# schemes.net
KiCad netlist of a schematic drawn in EasyEDA
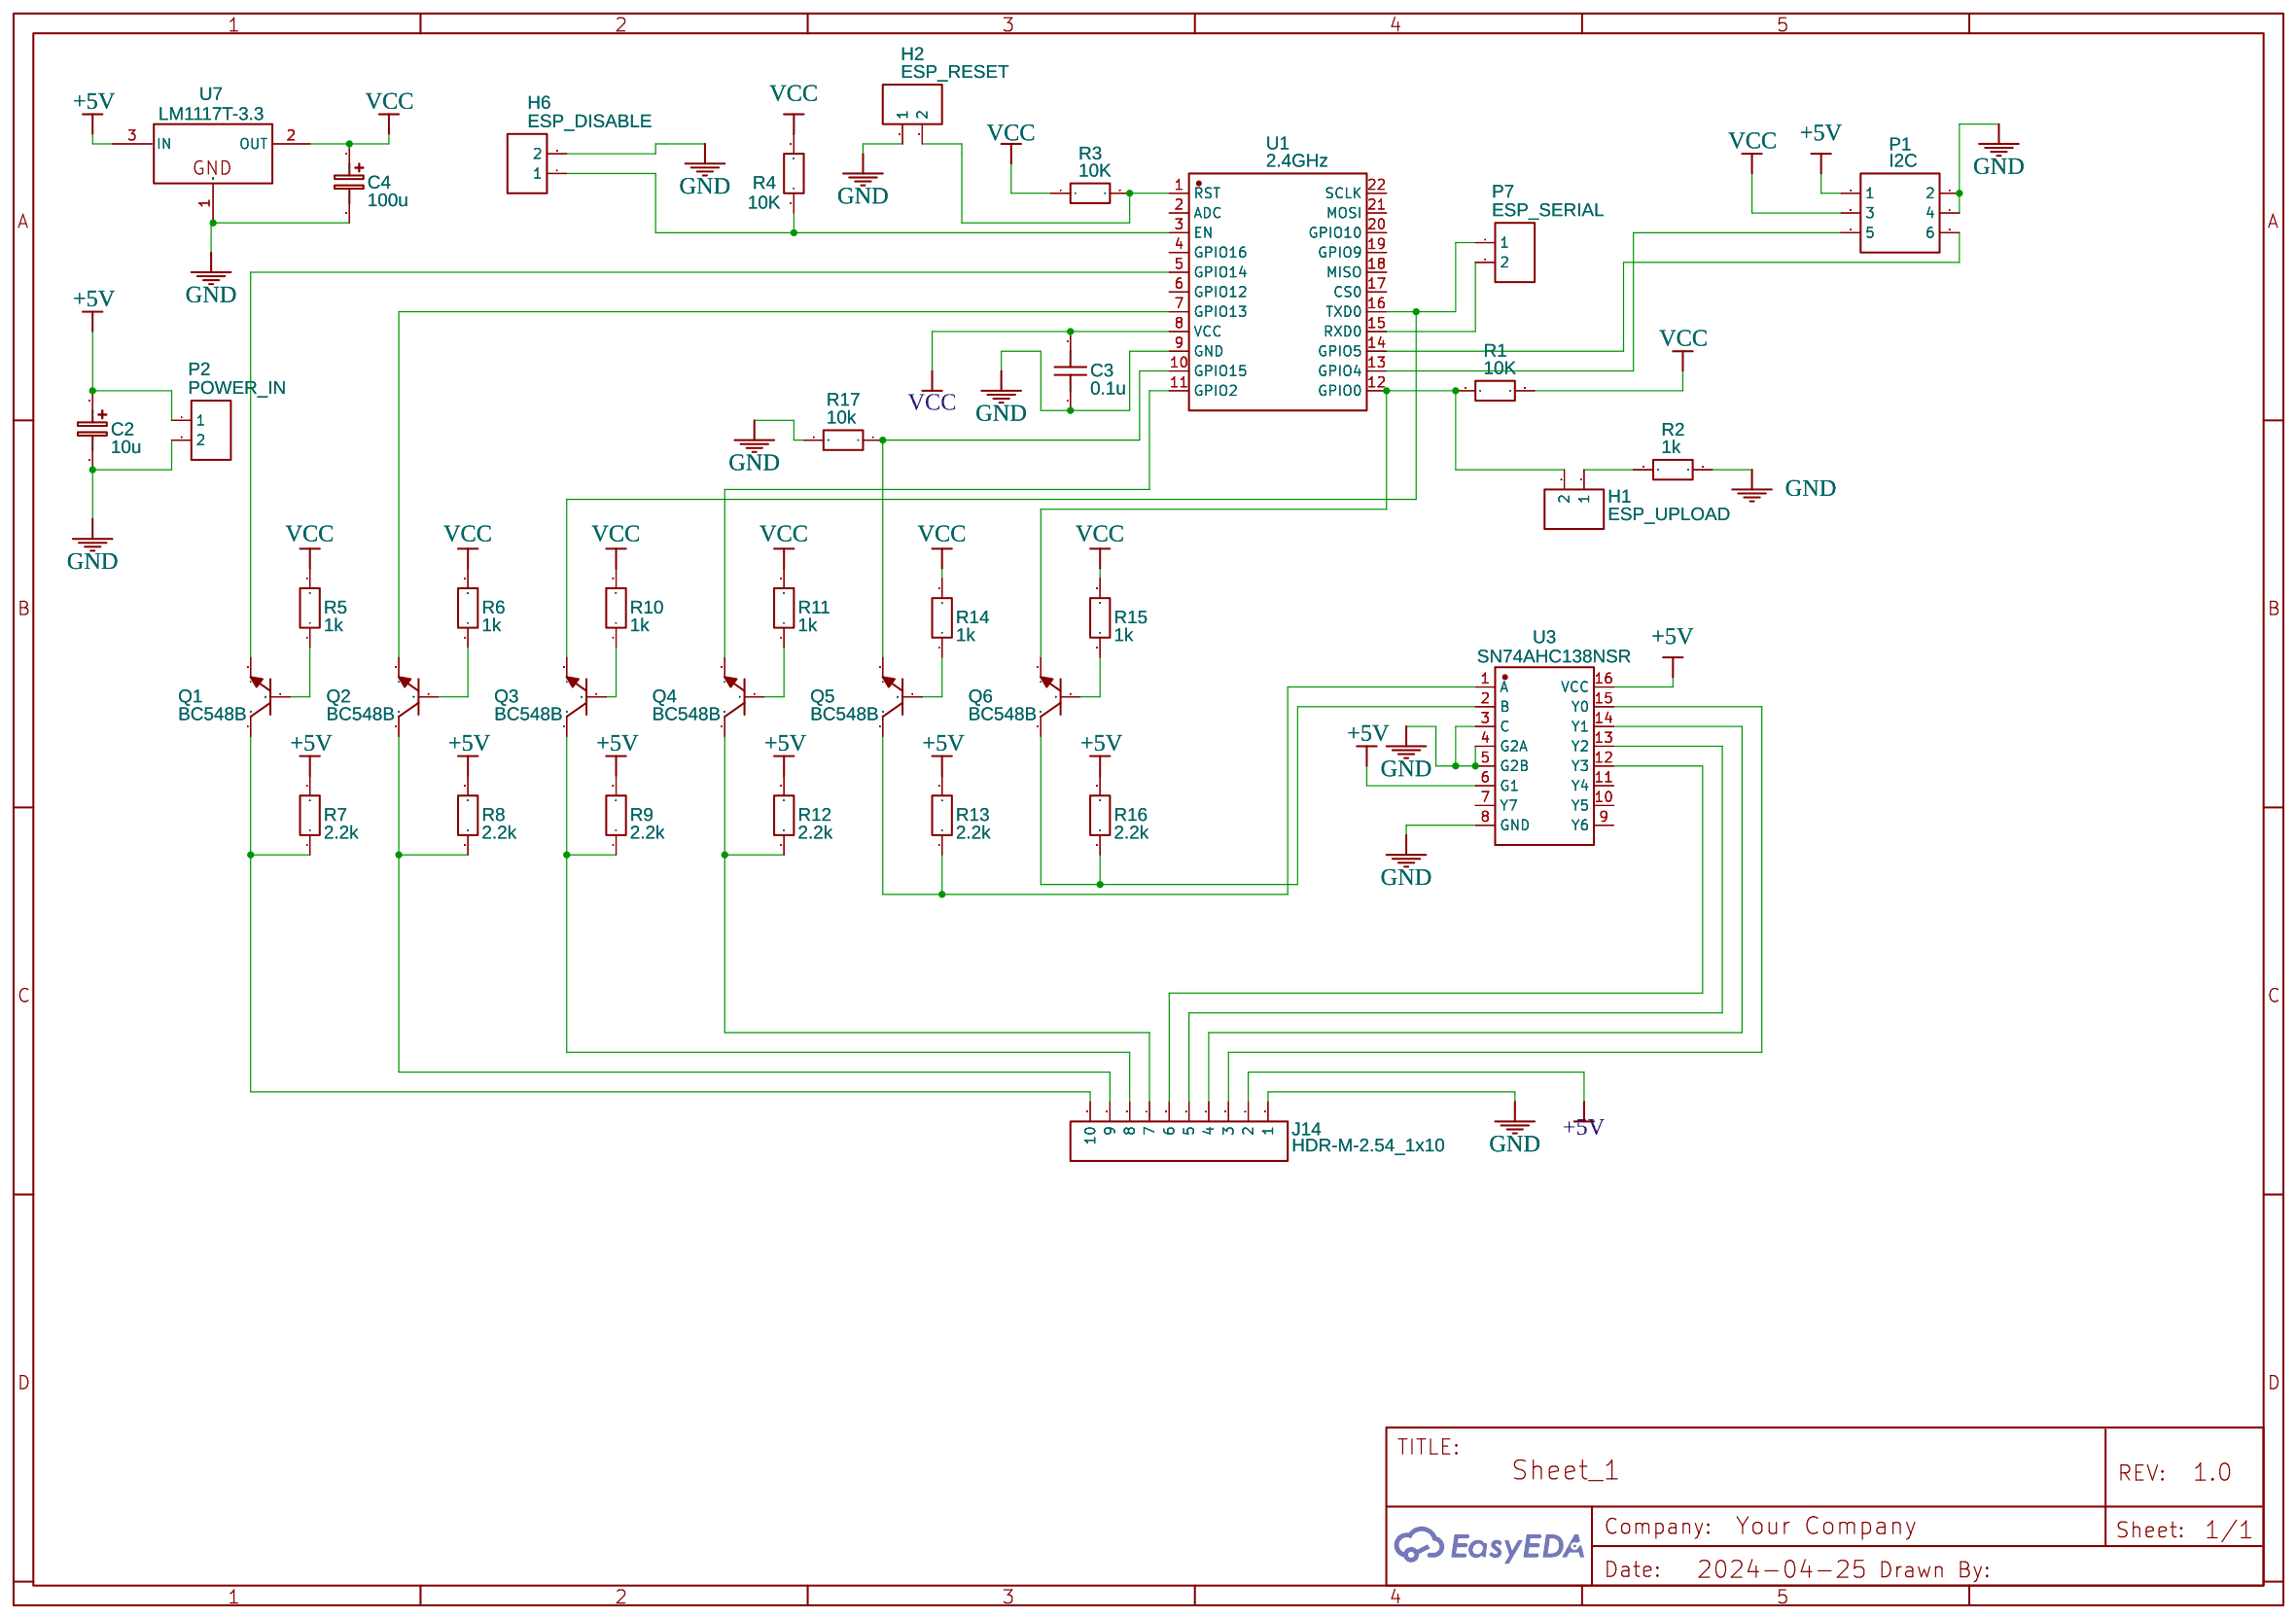
[diagram p0: Sheet_1]
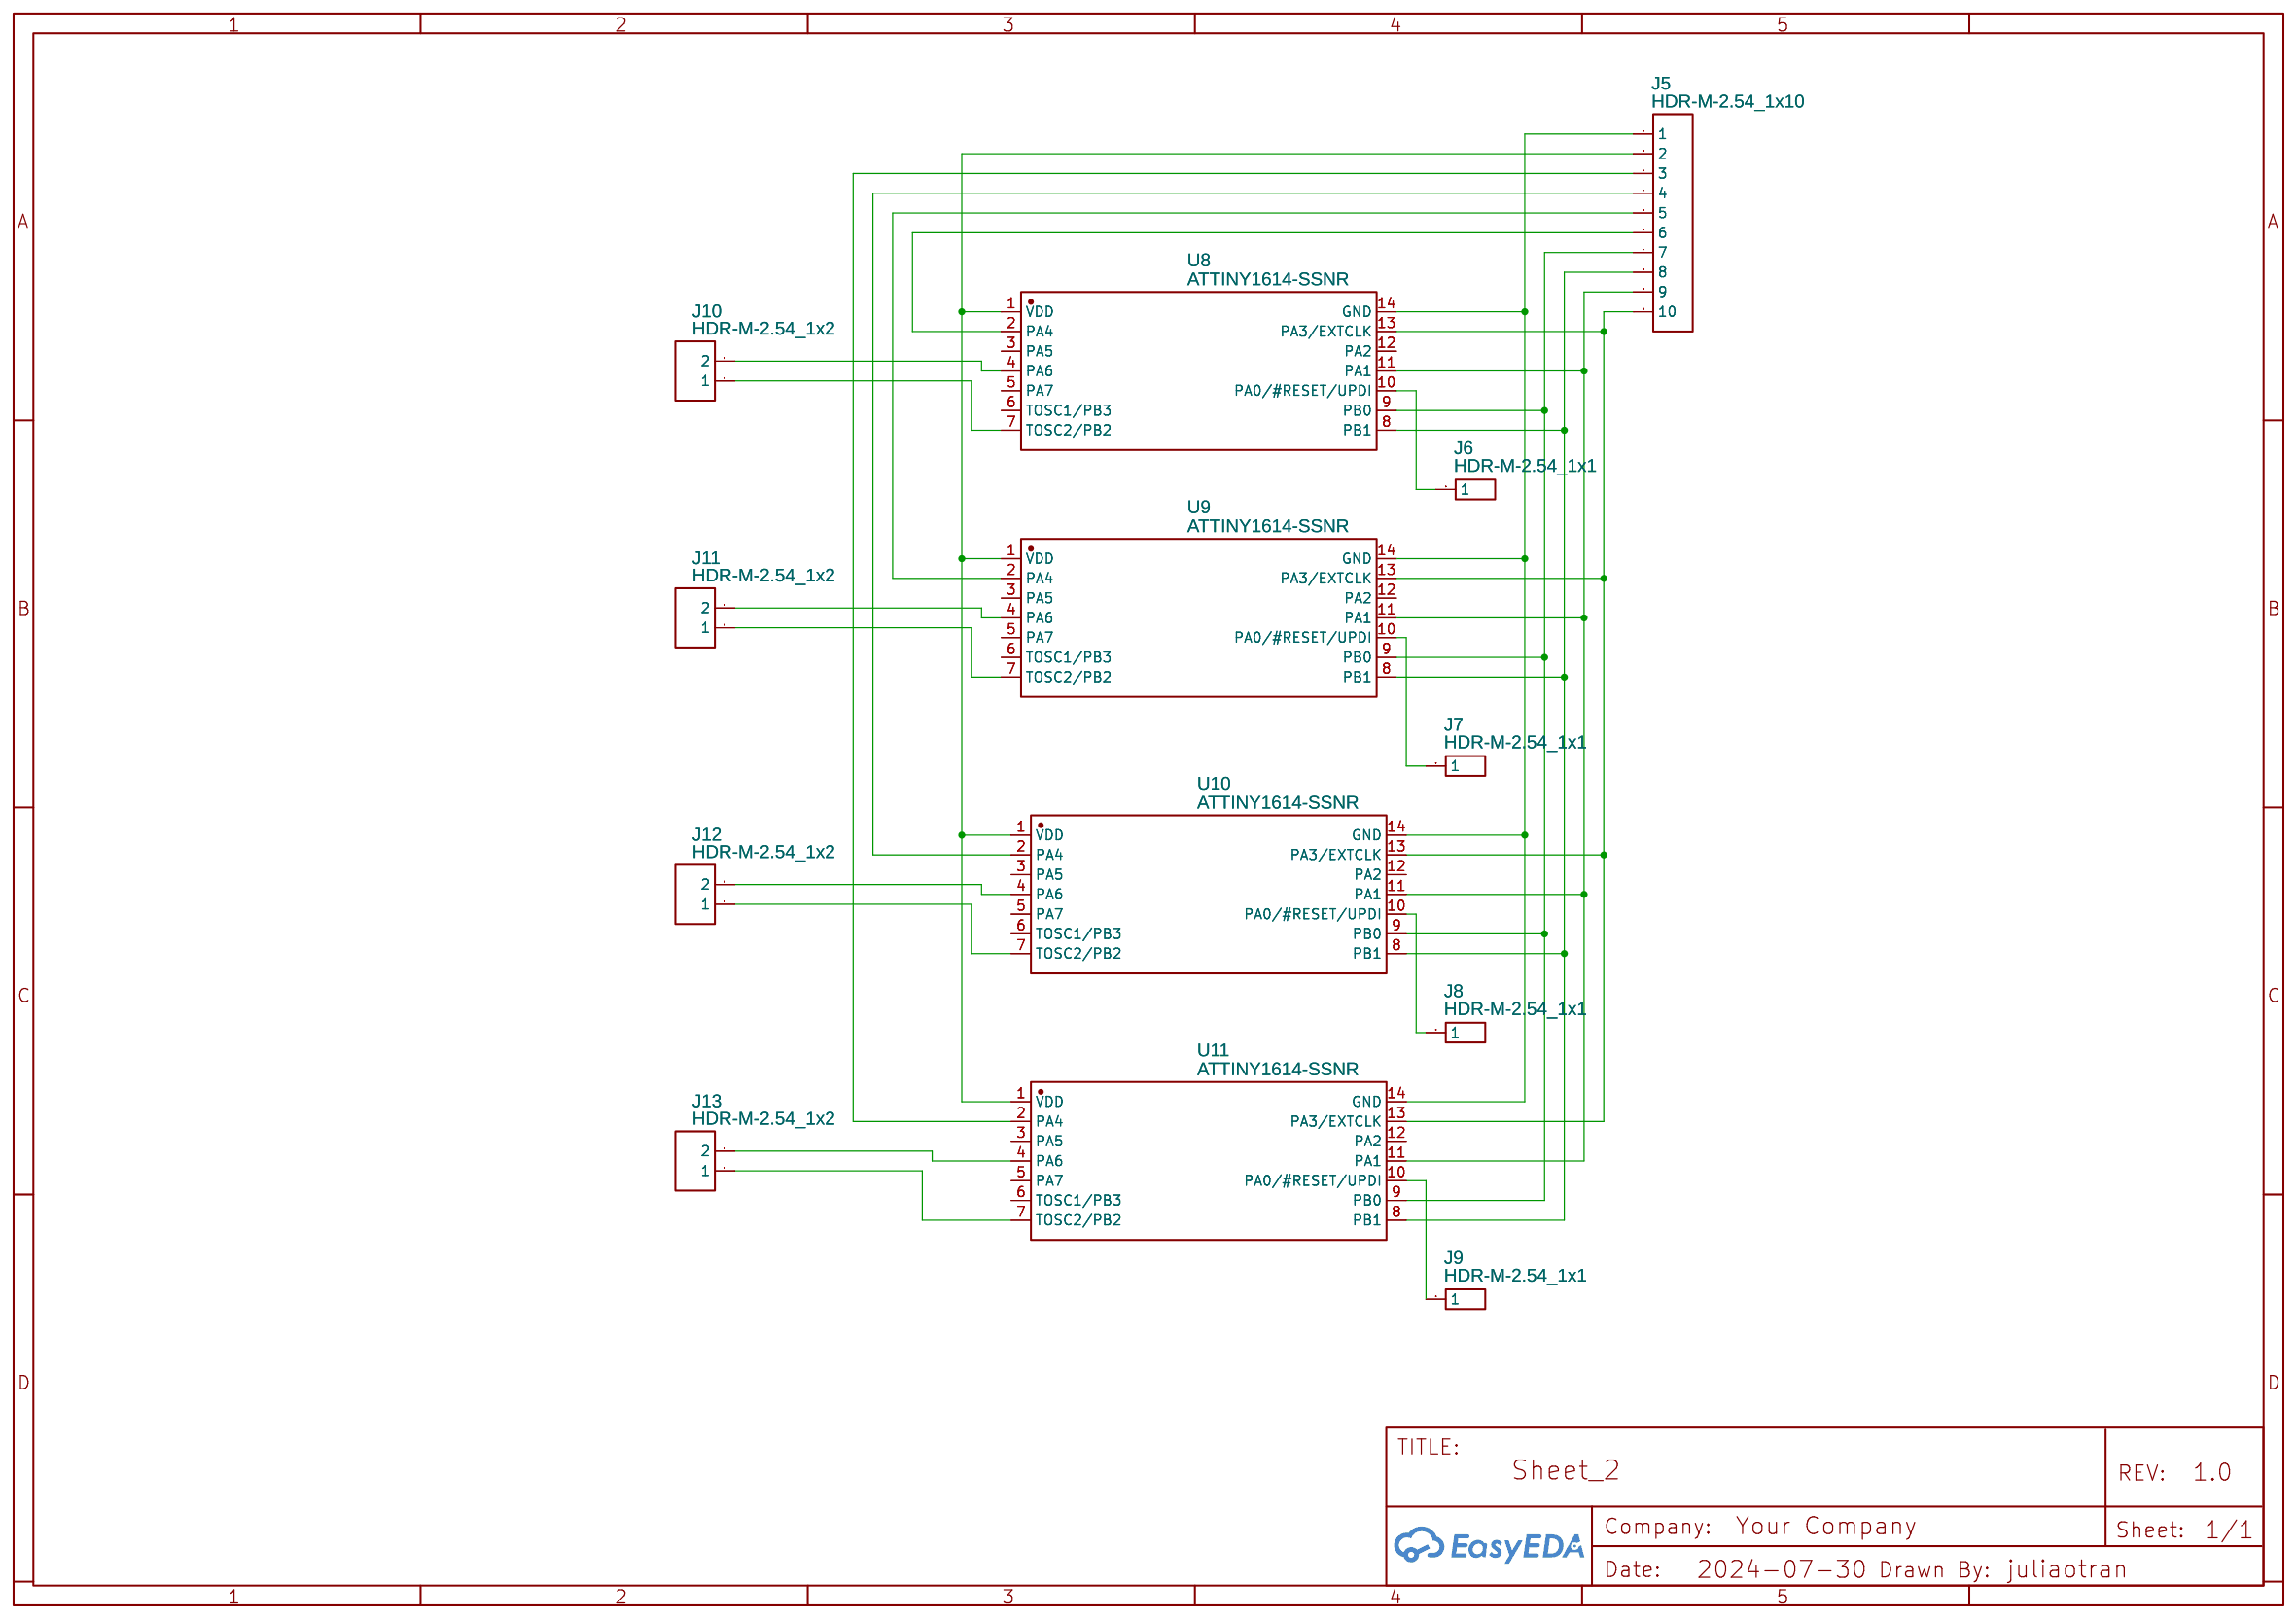
[diagram p1: Sheet_2]
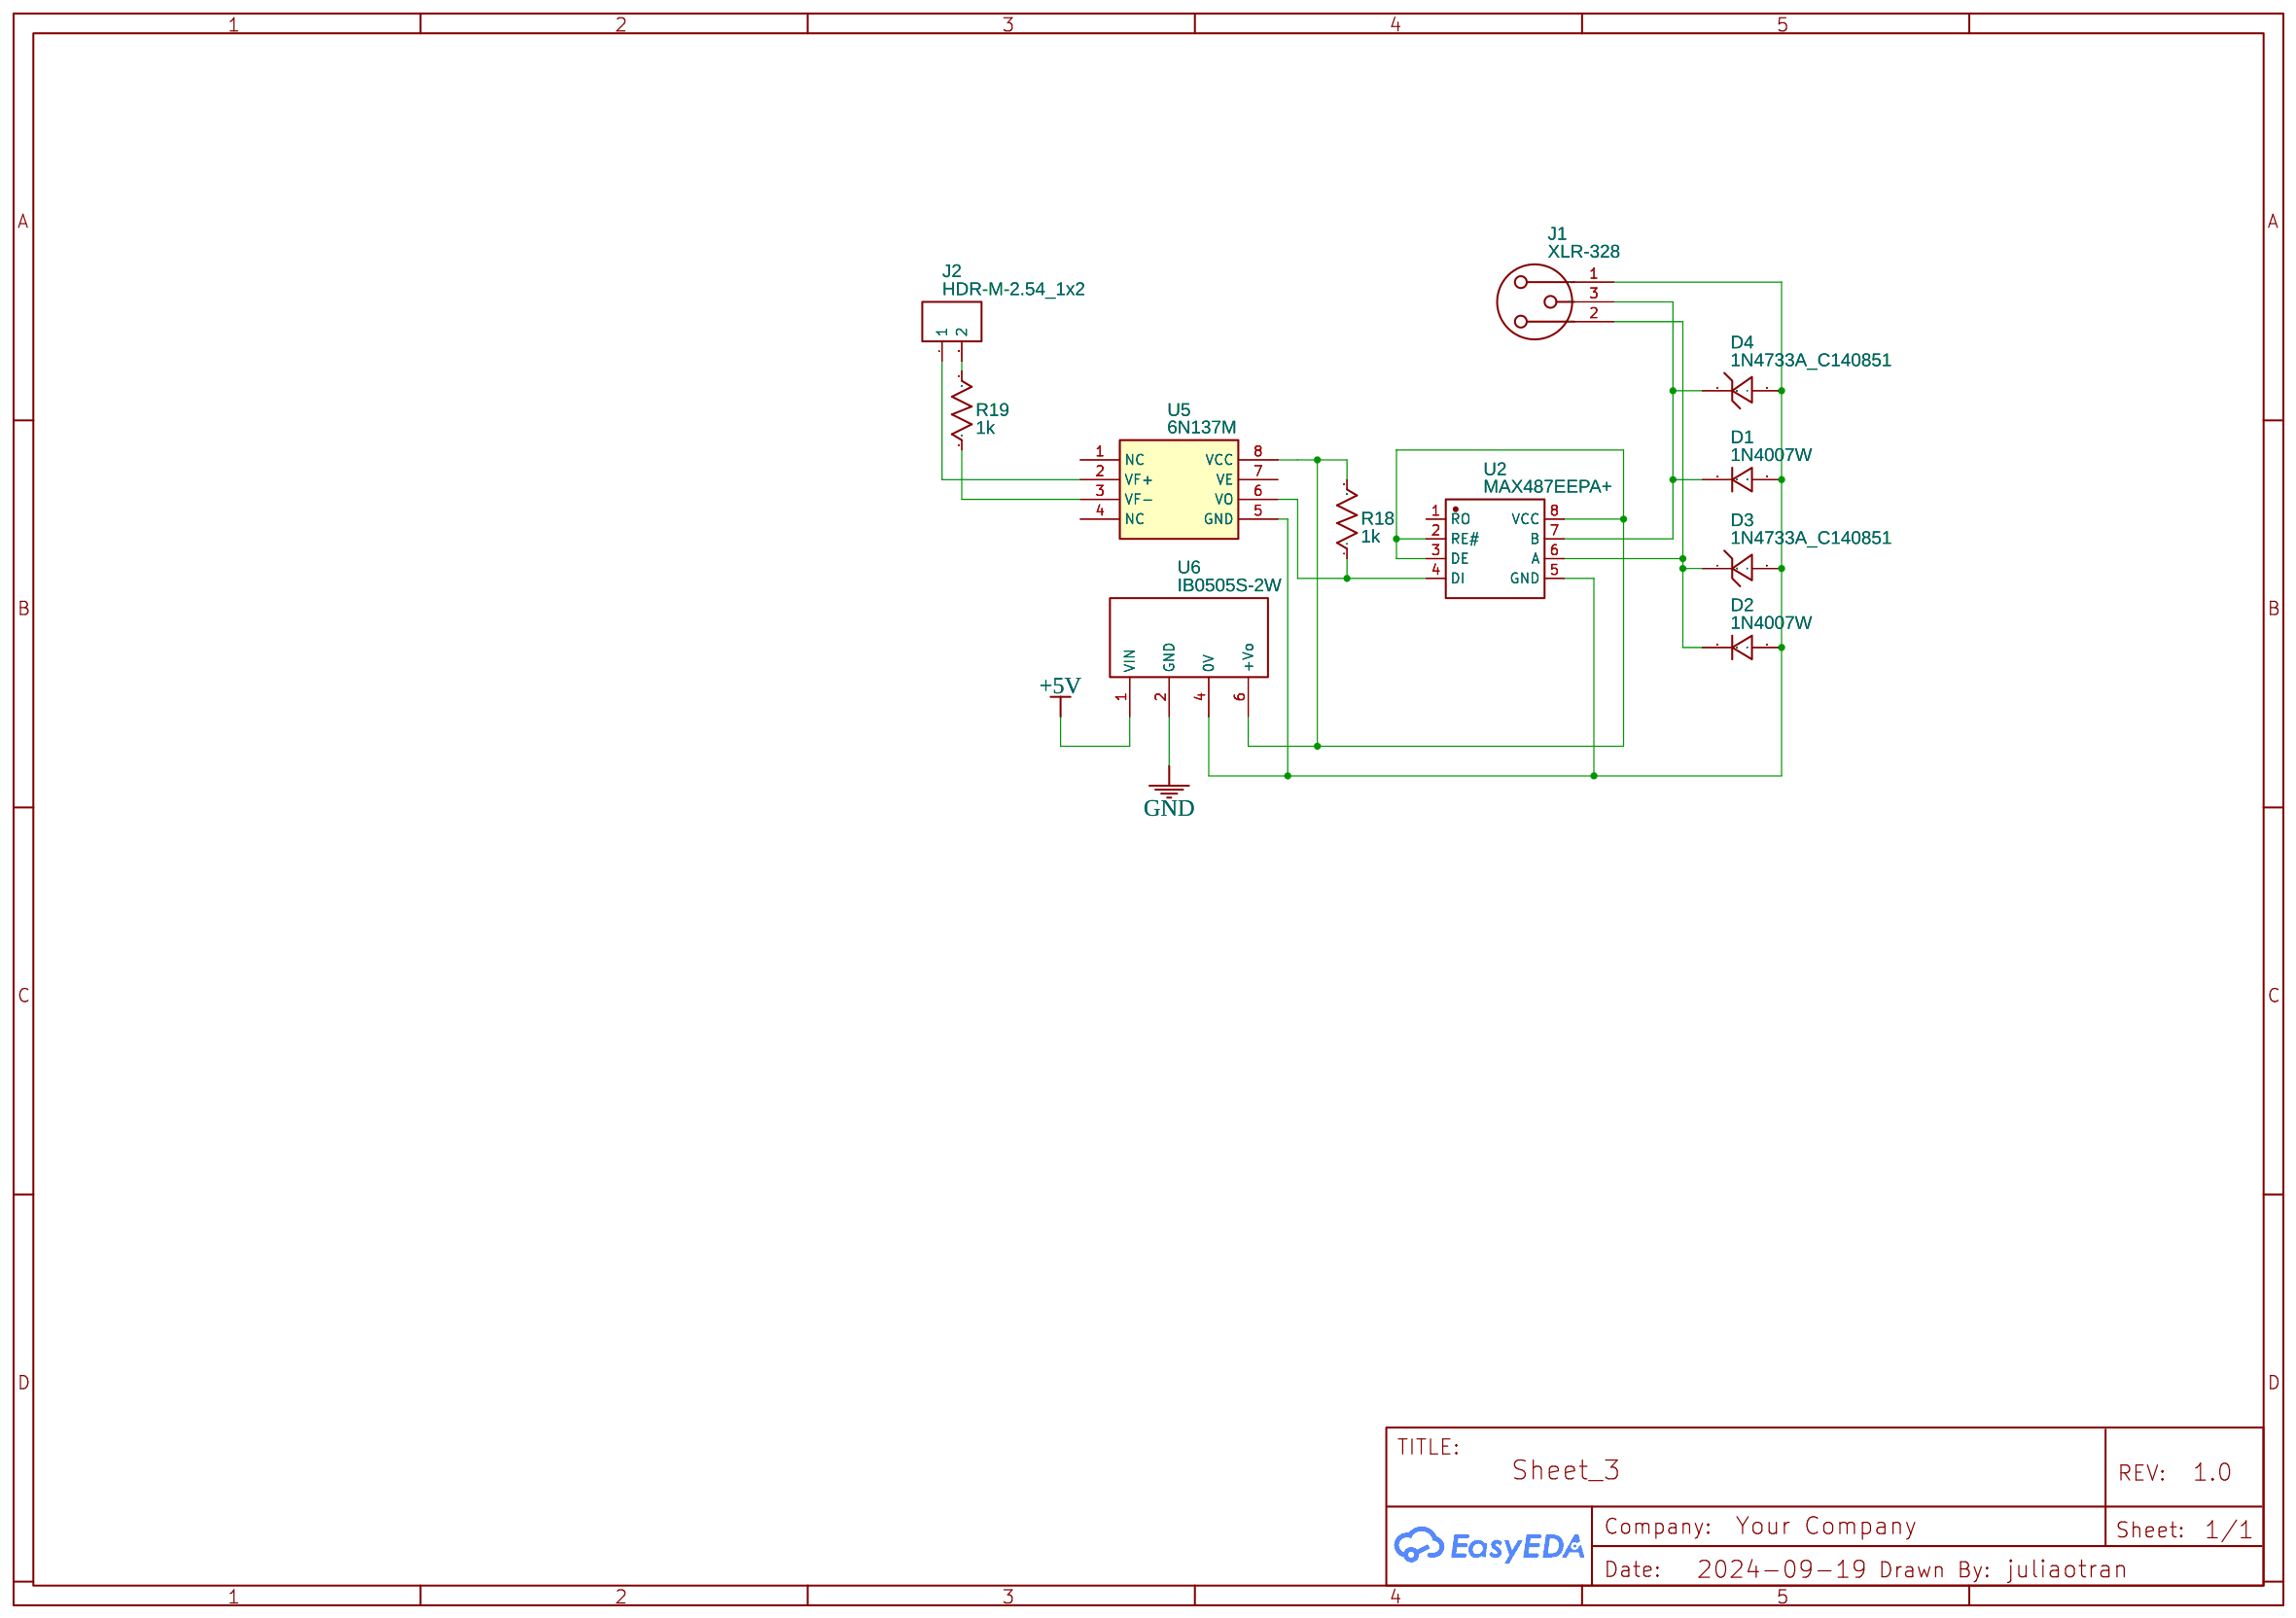
[diagram p2: Sheet_3]

(export (version "E")
  (design (tool "Eeschema 10.0.6"))
  (components
    (comp (ref "C2") (value "10u") (libsource (lib "") (part "CE_SMD_D4.0×H5.5_EU")))
    (comp (ref "C3") (value "0.1u") (libsource (lib "") (part "C_1206_US")))
    (comp (ref "C4") (value "100u") (libsource (lib "") (part "CE_TH_D5.0×F2.0_EU")))
    (comp (ref "H1") (value "ESP_UPLOAD") (libsource (lib "") (part "HDR-F-2.54_1x2")))
    (comp (ref "H2") (value "ESP_RESET") (libsource (lib "") (part "HDR-F-2.54_1x2_1")))
    (comp (ref "H6") (value "ESP_DISABLE") (libsource (lib "") (part "HDR-F-2.54_1x2_2")))
    (comp (ref "J14") (value "HDR-M-2.54_1x10") (libsource (lib "") (part "HDR-M-2.54_1x10")))
    (comp (ref "P1")
      (value "I2C")
      (fields (field (name "Manufacturer Part") "2X3 2.54mm IDC Box") (field (name "Manufacturer") "BOOMELE"))
      (libsource (lib "") (part "HDR-IDC-2.54-2X3P"))
    )
    (comp (ref "P2") (value "POWER_IN") (libsource (lib "") (part "CONN-TH_2P-P5.00")))
    (comp (ref "P7") (value "ESP_SERIAL") (libsource (lib "") (part "CONN-TH_2P-P5.00")))
    (comp (ref "Q1")
      (value "BC548B")
      (fields (field (name "Manufacturer Part") "BC548") (field (name "Manufacturer") "CJ(江苏长电/长晶)"))
      (libsource (lib "") (part "BC548B"))
    )
    (comp (ref "Q2")
      (value "BC548B")
      (fields (field (name "Manufacturer Part") "BC548") (field (name "Manufacturer") "CJ(江苏长电/长晶)"))
      (libsource (lib "") (part "BC548B"))
    )
    (comp (ref "Q3")
      (value "BC548B")
      (fields (field (name "Manufacturer Part") "BC548") (field (name "Manufacturer") "CJ(江苏长电/长晶)"))
      (libsource (lib "") (part "BC548B"))
    )
    (comp (ref "Q4")
      (value "BC548B")
      (fields (field (name "Manufacturer Part") "BC548") (field (name "Manufacturer") "CJ(江苏长电/长晶)"))
      (libsource (lib "") (part "BC548B"))
    )
    (comp (ref "Q5")
      (value "BC548B")
      (fields (field (name "Manufacturer Part") "BC548") (field (name "Manufacturer") "CJ(江苏长电/长晶)"))
      (libsource (lib "") (part "BC548B"))
    )
    (comp (ref "Q6")
      (value "BC548B")
      (fields (field (name "Manufacturer Part") "BC548") (field (name "Manufacturer") "CJ(江苏长电/长晶)"))
      (libsource (lib "") (part "BC548B"))
    )
    (comp (ref "R1") (value "10K") (libsource (lib "") (part "R_0603_EU_1")))
    (comp (ref "R2") (value "1k") (libsource (lib "") (part "R_0603_EU_1")))
    (comp (ref "R3") (value "10K") (libsource (lib "") (part "R_0603_EU_1")))
    (comp (ref "R4") (value "10K") (libsource (lib "") (part "R_0603_EU")))
    (comp (ref "R5") (value "1k") (libsource (lib "") (part "R_0603_EU")))
    (comp (ref "R6") (value "1k") (libsource (lib "") (part "R_0603_EU")))
    (comp (ref "R7") (value "2.2k") (libsource (lib "") (part "R_0603_EU")))
    (comp (ref "R8") (value "2.2k") (libsource (lib "") (part "R_0603_EU")))
    (comp (ref "R9") (value "2.2k") (libsource (lib "") (part "R_0603_EU")))
    (comp (ref "R10") (value "1k") (libsource (lib "") (part "R_0603_EU")))
    (comp (ref "R11") (value "1k") (libsource (lib "") (part "R_0603_EU")))
    (comp (ref "R12") (value "2.2k") (libsource (lib "") (part "R_0603_EU")))
    (comp (ref "R13") (value "2.2k") (libsource (lib "") (part "R_0603_EU")))
    (comp (ref "R14") (value "1k") (libsource (lib "") (part "R_0603_EU")))
    (comp (ref "R15") (value "1k") (libsource (lib "") (part "R_0603_EU")))
    (comp (ref "R16") (value "2.2k") (libsource (lib "") (part "R_0603_EU")))
    (comp (ref "R17") (value "10k") (libsource (lib "") (part "R_0603_EU_2")))
    (comp (ref "U1")
      (value "2.4GHz")
      (fields
        (field (name "Manufacturer Part") "ESP-12F(ESP8266MOD)")
        (field (name "Manufacturer") "Ai-Thinker(安信可)")
      )
      (libsource (lib "") (part "ESP-12F(ESP8266MOD)"))
    )
    (comp (ref "U3")
      (value "SN74AHC138NSR")
      (fields (field (name "Manufacturer") "TI(德州仪器)"))
      (libsource (lib "") (part "SN74AHC138NSR"))
    )
    (comp (ref "U7")
      (value "LM1117T-3.3")
      (fields (field (name "Manufacturer") "HGSEMI(华冠)"))
      (libsource (lib "") (part "LM1117T-3.3"))
    )
    (comp (ref "J5") (value "HDR-M-2.54_1x10") (libsource (lib "") (part "HDR-M-2.54_1x10")))
    (comp (ref "J6") (value "HDR-M-2.54_1x1") (libsource (lib "") (part "HDR-M-2.54_1x1")))
    (comp (ref "J7") (value "HDR-M-2.54_1x1") (libsource (lib "") (part "HDR-M-2.54_1x1")))
    (comp (ref "J8") (value "HDR-M-2.54_1x1") (libsource (lib "") (part "HDR-M-2.54_1x1")))
    (comp (ref "J9") (value "HDR-M-2.54_1x1") (libsource (lib "") (part "HDR-M-2.54_1x1")))
    (comp (ref "J10") (value "HDR-M-2.54_1x2") (libsource (lib "") (part "HDR-M-2.54_1x2")))
    (comp (ref "J11") (value "HDR-M-2.54_1x2") (libsource (lib "") (part "HDR-M-2.54_1x2")))
    (comp (ref "J12") (value "HDR-M-2.54_1x2") (libsource (lib "") (part "HDR-M-2.54_1x2")))
    (comp (ref "J13") (value "HDR-M-2.54_1x2") (libsource (lib "") (part "HDR-M-2.54_1x2")))
    (comp (ref "U8")
      (value "ATTINY1614-SSNR")
      (fields (field (name "Manufacturer") "MICROCHIP(美国微芯)"))
      (libsource (lib "") (part "ATTINY1614-SSNR"))
    )
    (comp (ref "U9")
      (value "ATTINY1614-SSNR")
      (fields (field (name "Manufacturer") "MICROCHIP(美国微芯)"))
      (libsource (lib "") (part "ATTINY1614-SSNR"))
    )
    (comp (ref "U10")
      (value "ATTINY1614-SSNR")
      (fields (field (name "Manufacturer") "MICROCHIP(美国微芯)"))
      (libsource (lib "") (part "ATTINY1614-SSNR"))
    )
    (comp (ref "U11")
      (value "ATTINY1614-SSNR")
      (fields (field (name "Manufacturer") "MICROCHIP(美国微芯)"))
      (libsource (lib "") (part "ATTINY1614-SSNR"))
    )
    (comp (ref "D1")
      (value "1N4007W")
      (fields (field (name "Manufacturer") "BLUE ROCKET"))
      (libsource (lib "") (part "1N4007W"))
    )
    (comp (ref "D2")
      (value "1N4007W")
      (fields (field (name "Manufacturer") "BLUE ROCKET"))
      (libsource (lib "") (part "1N4007W"))
    )
    (comp (ref "D3")
      (value "1N4733A_C140851")
      (fields (field (name "Manufacturer Part") "1N4733A") (field (name "Manufacturer") "onsemi(安森美)"))
      (libsource (lib "") (part "1N4733A_C140851"))
    )
    (comp (ref "D4")
      (value "1N4733A_C140851")
      (fields (field (name "Manufacturer Part") "1N4733A") (field (name "Manufacturer") "onsemi(安森美)"))
      (libsource (lib "") (part "1N4733A_C140851"))
    )
    (comp (ref "J1")
      (value "XLR-328")
      (fields (field (name "Manufacturer") "HOOYA(皓宇电子)"))
      (libsource (lib "") (part "XLR-328"))
    )
    (comp (ref "J2") (value "HDR-M-2.54_1x2") (libsource (lib "") (part "HDR-M-2.54_1x2")))
    (comp (ref "R18") (value "1k") (libsource (lib "") (part "R_0603_US")))
    (comp (ref "R19") (value "1k") (libsource (lib "") (part "R_0603_US")))
    (comp (ref "U2")
      (value "MAX487EEPA+")
      (fields (field (name "Manufacturer") "ADI(亚德诺)/MAXIM(美信)"))
      (libsource (lib "") (part "MAX487EEPA+"))
    )
    (comp (ref "U5")
      (value "6N137M")
      (fields (field (name "Manufacturer") "onsemi(安森美)"))
      (libsource (lib "") (part "6N137M"))
    )
    (comp (ref "U6")
      (value "IB0505S-2W")
      (fields (field (name "Manufacturer") "MORNSUN(金升阳)"))
      (libsource (lib "") (part "IB0505S-2W"))
    )
  )
  (nets
    (net (code "1") (name "+5V") (class "Default")
      (node (ref "C2") (pin "1") (pinfunction "1_1") (pintype "unspecified"))
      (node (ref "J14") (pin "2") (pinfunction "2_2") (pintype "unspecified"))
      (node (ref "P1") (pin "1") (pinfunction "1_1") (pintype "unspecified"))
      (node (ref "P2") (pin "1") (pinfunction "1_1") (pintype "unspecified"))
      (node (ref "R12") (pin "2") (pinfunction "2_2") (pintype "unspecified"))
      (node (ref "R13") (pin "2") (pinfunction "2_2") (pintype "unspecified"))
      (node (ref "R16") (pin "2") (pinfunction "2_2") (pintype "unspecified"))
      (node (ref "R7") (pin "2") (pinfunction "2_2") (pintype "unspecified"))
      (node (ref "R8") (pin "2") (pinfunction "2_2") (pintype "unspecified"))
      (node (ref "R9") (pin "2") (pinfunction "2_2") (pintype "unspecified"))
      (node (ref "U3") (pin "16") (pinfunction "VCC_16") (pintype "unspecified"))
      (node (ref "U3") (pin "6") (pinfunction "G1_6") (pintype "unspecified"))
      (node (ref "U6") (pin "1") (pinfunction "VIN_1") (pintype "unspecified"))
      (node (ref "U7") (pin "3") (pinfunction "IN_3") (pintype "unspecified"))
    )
    (net (code "2") (name "GND") (class "Default")
      (node (ref "C2") (pin "2") (pinfunction "2_2") (pintype "unspecified"))
      (node (ref "C3") (pin "1") (pinfunction "1_1") (pintype "unspecified"))
      (node (ref "C4") (pin "2") (pinfunction "2_2") (pintype "unspecified"))
      (node (ref "H2") (pin "1") (pinfunction "1_1") (pintype "input"))
      (node (ref "H6") (pin "2") (pinfunction "2_2") (pintype "input"))
      (node (ref "J14") (pin "1") (pinfunction "1_1") (pintype "unspecified"))
      (node (ref "P1") (pin "2") (pinfunction "2_2") (pintype "unspecified"))
      (node (ref "P1") (pin "4") (pinfunction "4_4") (pintype "unspecified"))
      (node (ref "P2") (pin "2") (pinfunction "2_2") (pintype "unspecified"))
      (node (ref "R17") (pin "2") (pinfunction "2_2") (pintype "unspecified"))
      (node (ref "R2") (pin "2") (pinfunction "2_2") (pintype "unspecified"))
      (node (ref "U1") (pin "9") (pinfunction "GND_9") (pintype "unspecified"))
      (node (ref "U3") (pin "3") (pinfunction "C_3") (pintype "unspecified"))
      (node (ref "U3") (pin "4") (pinfunction "G2A_4") (pintype "unspecified"))
      (node (ref "U3") (pin "5") (pinfunction "G2B_5") (pintype "unspecified"))
      (node (ref "U3") (pin "8") (pinfunction "GND_8") (pintype "unspecified"))
      (node (ref "U6") (pin "2") (pinfunction "GND_2") (pintype "unspecified"))
      (node (ref "U7") (pin "1") (pinfunction "GND_1") (pintype "unspecified"))
    )
    (net (code "3") (name "Net-(D3-A)") (class "Default")
      (node (ref "D1") (pin "2") (pinfunction "2_2") (pintype "unspecified"))
      (node (ref "D2") (pin "2") (pinfunction "2_2") (pintype "unspecified"))
      (node (ref "D3") (pin "2") (pinfunction "A_2") (pintype "unspecified"))
      (node (ref "D4") (pin "2") (pinfunction "A_2") (pintype "unspecified"))
      (node (ref "J1") (pin "1") (pinfunction "1_1") (pintype "unspecified"))
      (node (ref "U2") (pin "5") (pinfunction "GND_5") (pintype "unspecified"))
      (node (ref "U5") (pin "5") (pinfunction "GND_5") (pintype "unspecified"))
      (node (ref "U6") (pin "4") (pinfunction "0V_4") (pintype "unspecified"))
    )
    (net (code "4") (name "Net-(D3-C)") (class "Default")
      (node (ref "D2") (pin "1") (pinfunction "1_1") (pintype "unspecified"))
      (node (ref "D3") (pin "1") (pinfunction "C_1") (pintype "unspecified"))
      (node (ref "J1") (pin "2") (pinfunction "2_2") (pintype "unspecified"))
      (node (ref "U2") (pin "6") (pinfunction "A_6") (pintype "unspecified"))
    )
    (net (code "5") (name "Net-(D4-C)") (class "Default")
      (node (ref "D1") (pin "1") (pinfunction "1_1") (pintype "unspecified"))
      (node (ref "D4") (pin "1") (pinfunction "C_1") (pintype "unspecified"))
      (node (ref "J1") (pin "3") (pinfunction "3_3") (pintype "unspecified"))
      (node (ref "U2") (pin "7") (pinfunction "B_7") (pintype "unspecified"))
    )
    (net (code "6") (name "Net-(H1-Pad1)") (class "Default")
      (node (ref "H1") (pin "1") (pinfunction "1_1") (pintype "input"))
      (node (ref "R2") (pin "1") (pinfunction "1_1") (pintype "unspecified"))
    )
    (net (code "7") (name "Net-(J2-Pad2)") (class "Default")
      (node (ref "J2") (pin "2") (pinfunction "2_2") (pintype "unspecified"))
      (node (ref "R19") (pin "2") (pinfunction "2_2") (pintype "unspecified"))
    )
    (net (code "8") (name "Net-(Q1-B)") (class "Default")
      (node (ref "Q1") (pin "2") (pinfunction "B_2") (pintype "unspecified"))
      (node (ref "R5") (pin "1") (pinfunction "1_1") (pintype "unspecified"))
    )
    (net (code "9") (name "Net-(Q1-C)") (class "Default")
      (node (ref "J14") (pin "10") (pinfunction "10_10") (pintype "unspecified"))
      (node (ref "Q1") (pin "1") (pinfunction "C_1") (pintype "unspecified"))
      (node (ref "R7") (pin "1") (pinfunction "1_1") (pintype "unspecified"))
    )
    (net (code "10") (name "Net-(Q1-E)") (class "Default")
      (node (ref "Q1") (pin "3") (pinfunction "E_3") (pintype "unspecified"))
      (node (ref "U1") (pin "5") (pinfunction "GPIO14_5") (pintype "unspecified"))
    )
    (net (code "11") (name "Net-(Q2-B)") (class "Default")
      (node (ref "Q2") (pin "2") (pinfunction "B_2") (pintype "unspecified"))
      (node (ref "R6") (pin "1") (pinfunction "1_1") (pintype "unspecified"))
    )
    (net (code "12") (name "Net-(Q2-C)") (class "Default")
      (node (ref "J14") (pin "9") (pinfunction "9_9") (pintype "unspecified"))
      (node (ref "Q2") (pin "1") (pinfunction "C_1") (pintype "unspecified"))
      (node (ref "R8") (pin "1") (pinfunction "1_1") (pintype "unspecified"))
    )
    (net (code "13") (name "Net-(Q2-E)") (class "Default")
      (node (ref "Q2") (pin "3") (pinfunction "E_3") (pintype "unspecified"))
      (node (ref "U1") (pin "7") (pinfunction "GPIO13_7") (pintype "unspecified"))
    )
    (net (code "14") (name "Net-(Q3-B)") (class "Default")
      (node (ref "Q3") (pin "2") (pinfunction "B_2") (pintype "unspecified"))
      (node (ref "R10") (pin "1") (pinfunction "1_1") (pintype "unspecified"))
    )
    (net (code "15") (name "Net-(Q3-C)") (class "Default")
      (node (ref "J14") (pin "8") (pinfunction "8_8") (pintype "unspecified"))
      (node (ref "Q3") (pin "1") (pinfunction "C_1") (pintype "unspecified"))
      (node (ref "R9") (pin "1") (pinfunction "1_1") (pintype "unspecified"))
    )
    (net (code "16") (name "Net-(Q3-E)") (class "Default")
      (node (ref "P7") (pin "1") (pinfunction "1_1") (pintype "unspecified"))
      (node (ref "Q3") (pin "3") (pinfunction "E_3") (pintype "unspecified"))
      (node (ref "U1") (pin "16") (pinfunction "TXD0_16") (pintype "unspecified"))
    )
    (net (code "17") (name "Net-(Q4-B)") (class "Default")
      (node (ref "Q4") (pin "2") (pinfunction "B_2") (pintype "unspecified"))
      (node (ref "R11") (pin "1") (pinfunction "1_1") (pintype "unspecified"))
    )
    (net (code "18") (name "Net-(Q4-C)") (class "Default")
      (node (ref "J14") (pin "7") (pinfunction "7_7") (pintype "unspecified"))
      (node (ref "Q4") (pin "1") (pinfunction "C_1") (pintype "unspecified"))
      (node (ref "R12") (pin "1") (pinfunction "1_1") (pintype "unspecified"))
    )
    (net (code "19") (name "Net-(Q4-E)") (class "Default")
      (node (ref "Q4") (pin "3") (pinfunction "E_3") (pintype "unspecified"))
      (node (ref "U1") (pin "11") (pinfunction "GPIO2_11") (pintype "unspecified"))
    )
    (net (code "20") (name "Net-(Q5-B)") (class "Default")
      (node (ref "Q5") (pin "2") (pinfunction "B_2") (pintype "unspecified"))
      (node (ref "R14") (pin "1") (pinfunction "1_1") (pintype "unspecified"))
    )
    (net (code "21") (name "Net-(Q5-C)") (class "Default")
      (node (ref "Q5") (pin "1") (pinfunction "C_1") (pintype "unspecified"))
      (node (ref "R13") (pin "1") (pinfunction "1_1") (pintype "unspecified"))
      (node (ref "U3") (pin "1") (pinfunction "A_1") (pintype "unspecified"))
    )
    (net (code "22") (name "Net-(Q5-E)") (class "Default")
      (node (ref "Q5") (pin "3") (pinfunction "E_3") (pintype "unspecified"))
      (node (ref "R17") (pin "1") (pinfunction "1_1") (pintype "unspecified"))
      (node (ref "U1") (pin "10") (pinfunction "GPIO15_10") (pintype "unspecified"))
    )
    (net (code "23") (name "Net-(Q6-B)") (class "Default")
      (node (ref "Q6") (pin "2") (pinfunction "B_2") (pintype "unspecified"))
      (node (ref "R15") (pin "1") (pinfunction "1_1") (pintype "unspecified"))
    )
    (net (code "24") (name "Net-(Q6-C)") (class "Default")
      (node (ref "Q6") (pin "1") (pinfunction "C_1") (pintype "unspecified"))
      (node (ref "R16") (pin "1") (pinfunction "1_1") (pintype "unspecified"))
      (node (ref "U3") (pin "2") (pinfunction "B_2") (pintype "unspecified"))
    )
    (net (code "25") (name "Net-(Q6-E)") (class "Default")
      (node (ref "H1") (pin "2") (pinfunction "2_2") (pintype "input"))
      (node (ref "Q6") (pin "3") (pinfunction "E_3") (pintype "unspecified"))
      (node (ref "R1") (pin "1") (pinfunction "1_1") (pintype "unspecified"))
      (node (ref "U1") (pin "12") (pinfunction "GPIO0_12") (pintype "unspecified"))
    )
    (net (code "26") (name "Net-(U1-EN)") (class "Default")
      (node (ref "H6") (pin "1") (pinfunction "1_1") (pintype "input"))
      (node (ref "R4") (pin "1") (pinfunction "1_1") (pintype "unspecified"))
      (node (ref "U1") (pin "3") (pinfunction "EN_3") (pintype "unspecified"))
    )
    (net (code "27") (name "Net-(U1-GPIO4)") (class "Default")
      (node (ref "P1") (pin "5") (pinfunction "5_5") (pintype "unspecified"))
      (node (ref "U1") (pin "13") (pinfunction "GPIO4_13") (pintype "unspecified"))
    )
    (net (code "28") (name "Net-(U1-GPIO5)") (class "Default")
      (node (ref "P1") (pin "6") (pinfunction "6_6") (pintype "unspecified"))
      (node (ref "U1") (pin "14") (pinfunction "GPIO5_14") (pintype "unspecified"))
    )
    (net (code "29") (name "Net-(U1-RST)") (class "Default")
      (node (ref "H2") (pin "2") (pinfunction "2_2") (pintype "input"))
      (node (ref "R3") (pin "2") (pinfunction "2_2") (pintype "unspecified"))
      (node (ref "U1") (pin "1") (pinfunction "RST_1") (pintype "unspecified"))
    )
    (net (code "30") (name "Net-(U1-RXD0)") (class "Default")
      (node (ref "P7") (pin "2") (pinfunction "2_2") (pintype "unspecified"))
      (node (ref "U1") (pin "15") (pinfunction "RXD0_15") (pintype "unspecified"))
    )
    (net (code "31") (name "Net-(U2-DE)") (class "Default")
      (node (ref "R18") (pin "2") (pinfunction "2_2") (pintype "unspecified"))
      (node (ref "U2") (pin "2") (pinfunction "RE#_2") (pintype "unspecified"))
      (node (ref "U2") (pin "3") (pinfunction "DE_3") (pintype "unspecified"))
      (node (ref "U2") (pin "8") (pinfunction "VCC_8") (pintype "unspecified"))
      (node (ref "U5") (pin "8") (pinfunction "VCC_8") (pintype "unspecified"))
      (node (ref "U6") (pin "6") (pinfunction "+Vo_6") (pintype "unspecified"))
    )
    (net (code "32") (name "Net-(U2-DI)") (class "Default")
      (node (ref "R18") (pin "1") (pinfunction "1_1") (pintype "unspecified"))
      (node (ref "U2") (pin "4") (pinfunction "DI_4") (pintype "unspecified"))
      (node (ref "U5") (pin "6") (pinfunction "VO_6") (pintype "unspecified"))
    )
    (net (code "33") (name "Net-(U3-Y0)") (class "Default")
      (node (ref "J14") (pin "3") (pinfunction "3_3") (pintype "unspecified"))
      (node (ref "U3") (pin "15") (pinfunction "Y0_15") (pintype "unspecified"))
    )
    (net (code "34") (name "Net-(U3-Y1)") (class "Default")
      (node (ref "J14") (pin "4") (pinfunction "4_4") (pintype "unspecified"))
      (node (ref "U3") (pin "14") (pinfunction "Y1_14") (pintype "unspecified"))
    )
    (net (code "35") (name "Net-(U3-Y2)") (class "Default")
      (node (ref "J14") (pin "5") (pinfunction "5_5") (pintype "unspecified"))
      (node (ref "U3") (pin "13") (pinfunction "Y2_13") (pintype "unspecified"))
    )
    (net (code "36") (name "Net-(U3-Y3)") (class "Default")
      (node (ref "J14") (pin "6") (pinfunction "6_6") (pintype "unspecified"))
      (node (ref "U3") (pin "12") (pinfunction "Y3_12") (pintype "unspecified"))
    )
    (net (code "37") (name "Net-(U5-VF+)") (class "Default")
      (node (ref "J2") (pin "1") (pinfunction "1_1") (pintype "unspecified"))
      (node (ref "U5") (pin "2") (pinfunction "VF+_2") (pintype "unspecified"))
    )
    (net (code "38") (name "Net-(U5-VF-)") (class "Default")
      (node (ref "R19") (pin "1") (pinfunction "1_1") (pintype "unspecified"))
      (node (ref "U5") (pin "3") (pinfunction "VF-_3") (pintype "unspecified"))
    )
    (net (code "39") (name "Net-(U8-PA0{slash}#RESET{slash}UPDI)") (class "Default")
      (node (ref "J6") (pin "1") (pinfunction "1_1") (pintype "input"))
      (node (ref "U8") (pin "10") (pinfunction "PA0/#RESET/UPDI_10") (pintype "unspecified"))
    )
    (net (code "40") (name "Net-(U8-PA4)") (class "Default")
      (node (ref "J5") (pin "6") (pinfunction "6_6") (pintype "unspecified"))
      (node (ref "U8") (pin "2") (pinfunction "PA4_2") (pintype "unspecified"))
    )
    (net (code "41") (name "Net-(U8-PA6)") (class "Default")
      (node (ref "J10") (pin "2") (pinfunction "2_2") (pintype "unspecified"))
      (node (ref "U8") (pin "4") (pinfunction "PA6_4") (pintype "unspecified"))
    )
    (net (code "42") (name "Net-(U8-TOSC2{slash}PB2)") (class "Default")
      (node (ref "J10") (pin "1") (pinfunction "1_1") (pintype "unspecified"))
      (node (ref "U8") (pin "7") (pinfunction "TOSC2/PB2_7") (pintype "unspecified"))
    )
    (net (code "43") (name "Net-(U9-PA0{slash}#RESET{slash}UPDI)") (class "Default")
      (node (ref "J7") (pin "1") (pinfunction "1_1") (pintype "input"))
      (node (ref "U9") (pin "10") (pinfunction "PA0/#RESET/UPDI_10") (pintype "unspecified"))
    )
    (net (code "44") (name "Net-(U9-PA4)") (class "Default")
      (node (ref "J5") (pin "5") (pinfunction "5_5") (pintype "unspecified"))
      (node (ref "U9") (pin "2") (pinfunction "PA4_2") (pintype "unspecified"))
    )
    (net (code "45") (name "Net-(U9-PA6)") (class "Default")
      (node (ref "J11") (pin "2") (pinfunction "2_2") (pintype "unspecified"))
      (node (ref "U9") (pin "4") (pinfunction "PA6_4") (pintype "unspecified"))
    )
    (net (code "46") (name "Net-(U9-TOSC2{slash}PB2)") (class "Default")
      (node (ref "J11") (pin "1") (pinfunction "1_1") (pintype "unspecified"))
      (node (ref "U9") (pin "7") (pinfunction "TOSC2/PB2_7") (pintype "unspecified"))
    )
    (net (code "47") (name "Net-(U10-GND)") (class "Default")
      (node (ref "J5") (pin "1") (pinfunction "1_1") (pintype "unspecified"))
      (node (ref "U10") (pin "14") (pinfunction "GND_14") (pintype "unspecified"))
      (node (ref "U11") (pin "14") (pinfunction "GND_14") (pintype "unspecified"))
      (node (ref "U8") (pin "14") (pinfunction "GND_14") (pintype "unspecified"))
      (node (ref "U9") (pin "14") (pinfunction "GND_14") (pintype "unspecified"))
    )
    (net (code "48") (name "Net-(U10-PA0{slash}#RESET{slash}UPDI)") (class "Default")
      (node (ref "J8") (pin "1") (pinfunction "1_1") (pintype "input"))
      (node (ref "U10") (pin "10") (pinfunction "PA0/#RESET/UPDI_10") (pintype "unspecified"))
    )
    (net (code "49") (name "Net-(U10-PA1)") (class "Default")
      (node (ref "J5") (pin "9") (pinfunction "9_9") (pintype "unspecified"))
      (node (ref "U10") (pin "11") (pinfunction "PA1_11") (pintype "unspecified"))
      (node (ref "U11") (pin "11") (pinfunction "PA1_11") (pintype "unspecified"))
      (node (ref "U8") (pin "11") (pinfunction "PA1_11") (pintype "unspecified"))
      (node (ref "U9") (pin "11") (pinfunction "PA1_11") (pintype "unspecified"))
    )
    (net (code "50") (name "Net-(U10-PA3{slash}EXTCLK)") (class "Default")
      (node (ref "J5") (pin "10") (pinfunction "10_10") (pintype "unspecified"))
      (node (ref "U10") (pin "13") (pinfunction "PA3/EXTCLK_13") (pintype "unspecified"))
      (node (ref "U11") (pin "13") (pinfunction "PA3/EXTCLK_13") (pintype "unspecified"))
      (node (ref "U8") (pin "13") (pinfunction "PA3/EXTCLK_13") (pintype "unspecified"))
      (node (ref "U9") (pin "13") (pinfunction "PA3/EXTCLK_13") (pintype "unspecified"))
    )
    (net (code "51") (name "Net-(U10-PA4)") (class "Default")
      (node (ref "J5") (pin "4") (pinfunction "4_4") (pintype "unspecified"))
      (node (ref "U10") (pin "2") (pinfunction "PA4_2") (pintype "unspecified"))
    )
    (net (code "52") (name "Net-(U10-PA6)") (class "Default")
      (node (ref "J12") (pin "2") (pinfunction "2_2") (pintype "unspecified"))
      (node (ref "U10") (pin "4") (pinfunction "PA6_4") (pintype "unspecified"))
    )
    (net (code "53") (name "Net-(U10-PB0)") (class "Default")
      (node (ref "J5") (pin "7") (pinfunction "7_7") (pintype "unspecified"))
      (node (ref "U10") (pin "9") (pinfunction "PB0_9") (pintype "unspecified"))
      (node (ref "U11") (pin "9") (pinfunction "PB0_9") (pintype "unspecified"))
      (node (ref "U8") (pin "9") (pinfunction "PB0_9") (pintype "unspecified"))
      (node (ref "U9") (pin "9") (pinfunction "PB0_9") (pintype "unspecified"))
    )
    (net (code "54") (name "Net-(U10-PB1)") (class "Default")
      (node (ref "J5") (pin "8") (pinfunction "8_8") (pintype "unspecified"))
      (node (ref "U10") (pin "8") (pinfunction "PB1_8") (pintype "unspecified"))
      (node (ref "U11") (pin "8") (pinfunction "PB1_8") (pintype "unspecified"))
      (node (ref "U8") (pin "8") (pinfunction "PB1_8") (pintype "unspecified"))
      (node (ref "U9") (pin "8") (pinfunction "PB1_8") (pintype "unspecified"))
    )
    (net (code "55") (name "Net-(U10-TOSC2{slash}PB2)") (class "Default")
      (node (ref "J12") (pin "1") (pinfunction "1_1") (pintype "unspecified"))
      (node (ref "U10") (pin "7") (pinfunction "TOSC2/PB2_7") (pintype "unspecified"))
    )
    (net (code "56") (name "Net-(U10-VDD)") (class "Default")
      (node (ref "J5") (pin "2") (pinfunction "2_2") (pintype "unspecified"))
      (node (ref "U10") (pin "1") (pinfunction "VDD_1") (pintype "unspecified"))
      (node (ref "U11") (pin "1") (pinfunction "VDD_1") (pintype "unspecified"))
      (node (ref "U8") (pin "1") (pinfunction "VDD_1") (pintype "unspecified"))
      (node (ref "U9") (pin "1") (pinfunction "VDD_1") (pintype "unspecified"))
    )
    (net (code "57") (name "Net-(U11-PA0{slash}#RESET{slash}UPDI)") (class "Default")
      (node (ref "J9") (pin "1") (pinfunction "1_1") (pintype "input"))
      (node (ref "U11") (pin "10") (pinfunction "PA0/#RESET/UPDI_10") (pintype "unspecified"))
    )
    (net (code "58") (name "Net-(U11-PA4)") (class "Default")
      (node (ref "J5") (pin "3") (pinfunction "3_3") (pintype "unspecified"))
      (node (ref "U11") (pin "2") (pinfunction "PA4_2") (pintype "unspecified"))
    )
    (net (code "59") (name "Net-(U11-PA6)") (class "Default")
      (node (ref "J13") (pin "2") (pinfunction "2_2") (pintype "unspecified"))
      (node (ref "U11") (pin "4") (pinfunction "PA6_4") (pintype "unspecified"))
    )
    (net (code "60") (name "Net-(U11-TOSC2{slash}PB2)") (class "Default")
      (node (ref "J13") (pin "1") (pinfunction "1_1") (pintype "unspecified"))
      (node (ref "U11") (pin "7") (pinfunction "TOSC2/PB2_7") (pintype "unspecified"))
    )
    (net (code "61") (name "VCC") (class "Default")
      (node (ref "C3") (pin "2") (pinfunction "2_2") (pintype "unspecified"))
      (node (ref "C4") (pin "1") (pinfunction "1_1") (pintype "unspecified"))
      (node (ref "P1") (pin "3") (pinfunction "3_3") (pintype "unspecified"))
      (node (ref "R1") (pin "2") (pinfunction "2_2") (pintype "unspecified"))
      (node (ref "R10") (pin "2") (pinfunction "2_2") (pintype "unspecified"))
      (node (ref "R11") (pin "2") (pinfunction "2_2") (pintype "unspecified"))
      (node (ref "R14") (pin "2") (pinfunction "2_2") (pintype "unspecified"))
      (node (ref "R15") (pin "2") (pinfunction "2_2") (pintype "unspecified"))
      (node (ref "R3") (pin "1") (pinfunction "1_1") (pintype "unspecified"))
      (node (ref "R4") (pin "2") (pinfunction "2_2") (pintype "unspecified"))
      (node (ref "R5") (pin "2") (pinfunction "2_2") (pintype "unspecified"))
      (node (ref "R6") (pin "2") (pinfunction "2_2") (pintype "unspecified"))
      (node (ref "U1") (pin "8") (pinfunction "VCC_8") (pintype "unspecified"))
      (node (ref "U7") (pin "2") (pinfunction "OUT_2") (pintype "unspecified"))
    )
    (net (code "62") (name "unconnected-(U1-ADC-Pad2)") (class "Default")
      (node (ref "U1") (pin "2") (pinfunction "ADC_2") (pintype "unspecified"))
    )
    (net (code "63") (name "unconnected-(U1-CS0-Pad17)") (class "Default")
      (node (ref "U1") (pin "17") (pinfunction "CS0_17") (pintype "unspecified"))
    )
    (net (code "64") (name "unconnected-(U1-GPIO9-Pad19)") (class "Default")
      (node (ref "U1") (pin "19") (pinfunction "GPIO9_19") (pintype "unspecified"))
    )
    (net (code "65") (name "unconnected-(U1-GPIO10-Pad20)") (class "Default")
      (node (ref "U1") (pin "20") (pinfunction "GPIO10_20") (pintype "unspecified"))
    )
    (net (code "66") (name "unconnected-(U1-GPIO12-Pad6)") (class "Default")
      (node (ref "U1") (pin "6") (pinfunction "GPIO12_6") (pintype "unspecified"))
    )
    (net (code "67") (name "unconnected-(U1-GPIO16-Pad4)") (class "Default")
      (node (ref "U1") (pin "4") (pinfunction "GPIO16_4") (pintype "unspecified"))
    )
    (net (code "68") (name "unconnected-(U1-MISO-Pad18)") (class "Default")
      (node (ref "U1") (pin "18") (pinfunction "MISO_18") (pintype "unspecified"))
    )
    (net (code "69") (name "unconnected-(U1-MOSI-Pad21)") (class "Default")
      (node (ref "U1") (pin "21") (pinfunction "MOSI_21") (pintype "unspecified"))
    )
    (net (code "70") (name "unconnected-(U1-SCLK-Pad22)") (class "Default")
      (node (ref "U1") (pin "22") (pinfunction "SCLK_22") (pintype "unspecified"))
    )
    (net (code "71") (name "unconnected-(U2-RO-Pad1)") (class "Default")
      (node (ref "U2") (pin "1") (pinfunction "RO_1") (pintype "unspecified"))
    )
    (net (code "72") (name "unconnected-(U3-Y4-Pad11)") (class "Default")
      (node (ref "U3") (pin "11") (pinfunction "Y4_11") (pintype "unspecified"))
    )
    (net (code "73") (name "unconnected-(U3-Y5-Pad10)") (class "Default")
      (node (ref "U3") (pin "10") (pinfunction "Y5_10") (pintype "unspecified"))
    )
    (net (code "74") (name "unconnected-(U3-Y6-Pad9)") (class "Default")
      (node (ref "U3") (pin "9") (pinfunction "Y6_9") (pintype "unspecified"))
    )
    (net (code "75") (name "unconnected-(U3-Y7-Pad7)") (class "Default")
      (node (ref "U3") (pin "7") (pinfunction "Y7_7") (pintype "unspecified"))
    )
    (net (code "76") (name "unconnected-(U5-NC-Pad1)") (class "Default")
      (node (ref "U5") (pin "1") (pinfunction "NC_1") (pintype "unspecified"))
    )
    (net (code "77") (name "unconnected-(U5-NC-Pad4)") (class "Default")
      (node (ref "U5") (pin "4") (pinfunction "NC_4") (pintype "unspecified"))
    )
    (net (code "78") (name "unconnected-(U5-VE-Pad7)") (class "Default")
      (node (ref "U5") (pin "7") (pinfunction "VE_7") (pintype "unspecified"))
    )
    (net (code "79") (name "unconnected-(U8-PA2-Pad12)") (class "Default")
      (node (ref "U8") (pin "12") (pinfunction "PA2_12") (pintype "unspecified"))
    )
    (net (code "80") (name "unconnected-(U8-PA5-Pad3)") (class "Default")
      (node (ref "U8") (pin "3") (pinfunction "PA5_3") (pintype "unspecified"))
    )
    (net (code "81") (name "unconnected-(U8-PA7-Pad5)") (class "Default")
      (node (ref "U8") (pin "5") (pinfunction "PA7_5") (pintype "unspecified"))
    )
    (net (code "82") (name "unconnected-(U8-TOSC1{slash}PB3-Pad6)") (class "Default")
      (node (ref "U8") (pin "6") (pinfunction "TOSC1/PB3_6") (pintype "unspecified"))
    )
    (net (code "83") (name "unconnected-(U9-PA2-Pad12)") (class "Default")
      (node (ref "U9") (pin "12") (pinfunction "PA2_12") (pintype "unspecified"))
    )
    (net (code "84") (name "unconnected-(U9-PA5-Pad3)") (class "Default")
      (node (ref "U9") (pin "3") (pinfunction "PA5_3") (pintype "unspecified"))
    )
    (net (code "85") (name "unconnected-(U9-PA7-Pad5)") (class "Default")
      (node (ref "U9") (pin "5") (pinfunction "PA7_5") (pintype "unspecified"))
    )
    (net (code "86") (name "unconnected-(U9-TOSC1{slash}PB3-Pad6)") (class "Default")
      (node (ref "U9") (pin "6") (pinfunction "TOSC1/PB3_6") (pintype "unspecified"))
    )
    (net (code "87") (name "unconnected-(U10-PA2-Pad12)") (class "Default")
      (node (ref "U10") (pin "12") (pinfunction "PA2_12") (pintype "unspecified"))
    )
    (net (code "88") (name "unconnected-(U10-PA5-Pad3)") (class "Default")
      (node (ref "U10") (pin "3") (pinfunction "PA5_3") (pintype "unspecified"))
    )
    (net (code "89") (name "unconnected-(U10-PA7-Pad5)") (class "Default")
      (node (ref "U10") (pin "5") (pinfunction "PA7_5") (pintype "unspecified"))
    )
    (net (code "90") (name "unconnected-(U10-TOSC1{slash}PB3-Pad6)") (class "Default")
      (node (ref "U10") (pin "6") (pinfunction "TOSC1/PB3_6") (pintype "unspecified"))
    )
    (net (code "91") (name "unconnected-(U11-PA2-Pad12)") (class "Default")
      (node (ref "U11") (pin "12") (pinfunction "PA2_12") (pintype "unspecified"))
    )
    (net (code "92") (name "unconnected-(U11-PA5-Pad3)") (class "Default")
      (node (ref "U11") (pin "3") (pinfunction "PA5_3") (pintype "unspecified"))
    )
    (net (code "93") (name "unconnected-(U11-PA7-Pad5)") (class "Default")
      (node (ref "U11") (pin "5") (pinfunction "PA7_5") (pintype "unspecified"))
    )
    (net (code "94") (name "unconnected-(U11-TOSC1{slash}PB3-Pad6)") (class "Default")
      (node (ref "U11") (pin "6") (pinfunction "TOSC1/PB3_6") (pintype "unspecified"))
    )
  )
)
